# Protection_channel_A_Page_2.net
KiCad netlist of a schematic drawn in Altium Designer
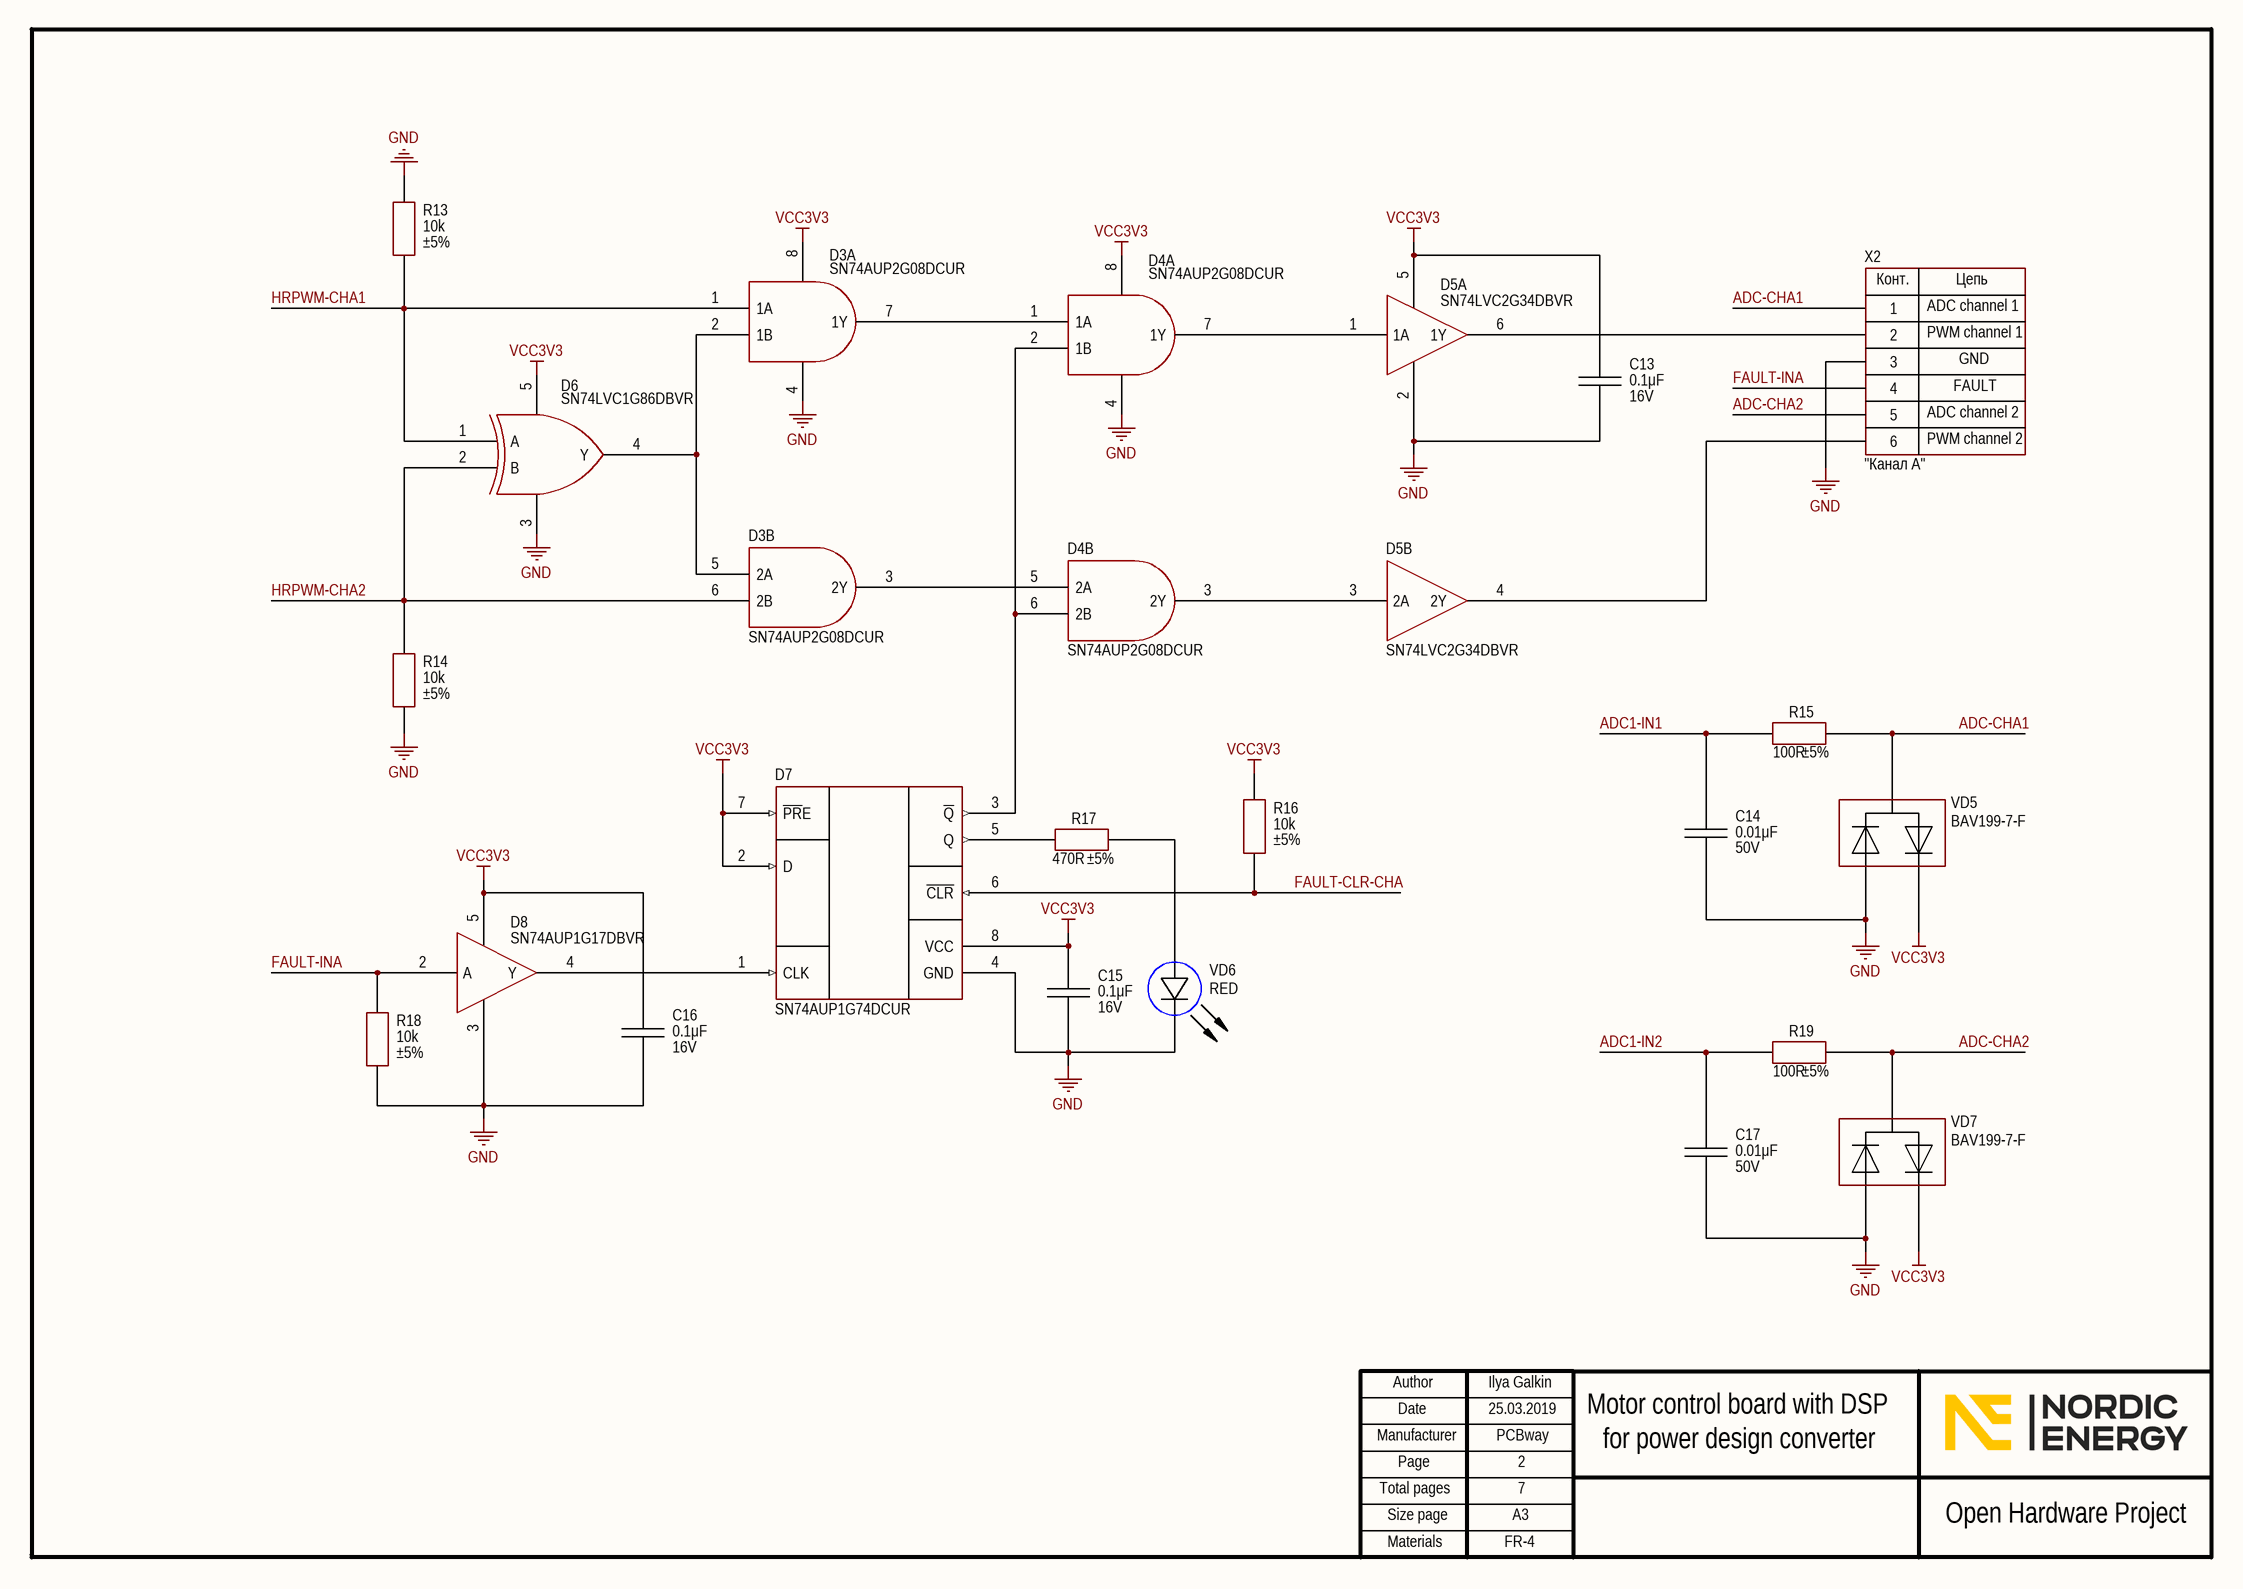
[diagram p0: Protection channel A. Page 2.SchDoc]

(export (version "E")
  (design (tool "Eeschema 10.0.6"))
  (components
    (comp (ref "C13")
      (value "0.1μF")
      (footprint "CAP: 0805")
      (fields
        (field (name "MANUFACTURER") "Yageo")
        (field (name "PARTNUMBER") "CC0805KRX7R7BB104")
        (field (name "VALUEMANUFACTURERPARTNUMBER") "Ceramic capacitor, 0.1μF, X7R, ±10%, 16V, 0805, -55...+125°C")
        (field (name "VOLTAGE") "16V")
      )
      (libsource (lib "Capacitor") (part "Ceramic_0805"))
    )
    (comp (ref "C14")
      (value "0.01μF")
      (footprint "CAP: 0805")
      (fields
        (field (name "MANUFACTURER") "Yageo")
        (field (name "PARTNUMBER") "CC0805KRX7R9BB103")
        (field (name "VALUEMANUFACTURERPARTNUMBER") "Ceramic capacitor, 0.01μF, X7R, ±10%, 50V, 0805, -55...+125°C")
        (field (name "VOLTAGE") "50V")
      )
      (libsource (lib "Capacitor") (part "Ceramic_0805"))
    )
    (comp (ref "C15")
      (value "0.1μF")
      (footprint "CAP: 0805")
      (fields
        (field (name "MANUFACTURER") "Yageo")
        (field (name "PARTNUMBER") "CC0805KRX7R7BB104")
        (field (name "VALUEMANUFACTURERPARTNUMBER") "Ceramic capacitor, 0.1μF, X7R, ±10%, 16V, 0805, -55...+125°C")
        (field (name "VOLTAGE") "16V")
      )
      (libsource (lib "Capacitor") (part "Ceramic_0805"))
    )
    (comp (ref "C16")
      (value "0.1μF")
      (footprint "CAP: 0805")
      (fields
        (field (name "MANUFACTURER") "Yageo")
        (field (name "PARTNUMBER") "CC0805KRX7R7BB104")
        (field (name "VALUEMANUFACTURERPARTNUMBER") "Ceramic capacitor, 0.1μF, X7R, ±10%, 16V, 0805, -55...+125°C")
        (field (name "VOLTAGE") "16V")
      )
      (libsource (lib "Capacitor") (part "Ceramic_0805"))
    )
    (comp (ref "C17")
      (value "0.01μF")
      (footprint "CAP: 0805")
      (fields
        (field (name "MANUFACTURER") "Yageo")
        (field (name "PARTNUMBER") "CC0805KRX7R9BB103")
        (field (name "VALUEMANUFACTURERPARTNUMBER") "Ceramic capacitor, 0.01μF, X7R, ±10%, 50V, 0805, -55...+125°C")
        (field (name "VOLTAGE") "50V")
      )
      (libsource (lib "Capacitor") (part "Ceramic_0805"))
    )
    (comp (ref "D3")
      (value "~")
      (footprint "8-VSSOP")
      (description "AND")
      (fields
        (field (name "MANUFACTURER") "Texas Instruments")
        (field (name "VALUEMANUFACTURERPARTNUMBER") "IC logic AND, 0.8...3.6V, -40...+855°C, 8-VSSOP")
        (field (name "PARTNUMBER") "SN74AUP2G08DCUR")
      )
      (libsource (lib "IC. Logic") (part "SN74AUP2G08DCUR"))
    )
    (comp (ref "D4")
      (value "~")
      (footprint "8-VSSOP")
      (description "AND")
      (fields
        (field (name "MANUFACTURER") "Texas Instruments")
        (field (name "VALUEMANUFACTURERPARTNUMBER") "IC logic AND, 0.8...3.6V, -40...+855°C, 8-VSSOP")
        (field (name "PARTNUMBER") "SN74AUP2G08DCUR")
      )
      (libsource (lib "IC. Logic") (part "SN74AUP2G08DCUR"))
    )
    (comp (ref "D5")
      (value "~")
      (footprint "SOT23-6")
      (description "Buffer")
      (fields
        (field (name "MANUFACTURER") "Texas Instruments")
        (field (name "VALUEMANUFACTURERPARTNUMBER") "IC logic buffer, 1.65...5.5V, -40...+125°C, SOT23-6")
        (field (name "PARTNUMBER") "SN74LVC2G34DBVR")
      )
      (libsource (lib "IC. Logic") (part "SN74LVC2G34DBVR"))
    )
    (comp (ref "D6")
      (value "~")
      (footprint "SOT23-5")
      (description "XOR")
      (fields
        (field (name "MANUFACTURER") "Texas Instruments")
        (field (name "VALUEMANUFACTURERPARTNUMBER") "IC logic XOR, 1.65...5.5V, -40...+125°C, SOT23-5")
        (field (name "PARTNUMBER") "SN74LVC1G86DBVR")
      )
      (libsource (lib "IC. Logic") (part "SN74LVC1G86DBVR"))
    )
    (comp (ref "D7")
      (value "~")
      (footprint "8-VSSOP")
      (description "D-trigger")
      (fields
        (field (name "MANUFACTURER") "Texas Instruments")
        (field (name "VALUEMANUFACTURERPARTNUMBER") "ICtrigger D-type, 0.8...3.6V, -40...+85°C, 8-VSSOP")
        (field (name "PARTNUMBER") "SN74AUP1G74DCUR")
      )
      (libsource (lib "IC. Logic") (part "SN74AUP1G74DCUR"))
    )
    (comp (ref "D8")
      (value "~")
      (footprint "SOT23-5")
      (description "Schmitt trigger")
      (fields
        (field (name "MANUFACTURER") "Texas Instruments")
        (field (name "VALUEMANUFACTURERPARTNUMBER") "IC Schmitt trigger, 0.8...3.6V, -40...+85°C, SOT23-6")
        (field (name "PARTNUMBER") "SN74AUP1G17DBVR")
      )
      (libsource (lib "IC. Logic") (part "SN74AUP1G17DBVR"))
    )
    (comp (ref "R13")
      (value "10k")
      (footprint "RES: 0805")
      (fields
        (field (name "MANUFACTURER") "Yageo")
        (field (name "PARTNUMBER") "RC0805JR-0710KL")
        (field (name "VALUEMANUFACTURERPARTNUMBER") "Resistor film, 10k, ±5%, 0805, 0.125W, -55...+125°C")
        (field (name "TOLERANCE") "±5%")
      )
      (libsource (lib "Resistor") (part "Resistor_0805"))
    )
    (comp (ref "R14")
      (value "10k")
      (footprint "RES: 0805")
      (fields
        (field (name "MANUFACTURER") "Yageo")
        (field (name "PARTNUMBER") "RC0805JR-0710KL")
        (field (name "VALUEMANUFACTURERPARTNUMBER") "Resistor film, 10k, ±5%, 0805, 0.125W, -55...+125°C")
        (field (name "TOLERANCE") "±5%")
      )
      (libsource (lib "Resistor") (part "Resistor_0805"))
    )
    (comp (ref "R15")
      (value "100R")
      (footprint "RES: 0805")
      (fields
        (field (name "MANUFACTURER") "Yageo")
        (field (name "PARTNUMBER") "RC0805JR-07100RL")
        (field (name "VALUEMANUFACTURERPARTNUMBER") "Resistor film, 100R, ±5%, 0805, 0.125W, -55...+125°C")
        (field (name "TOLERANCE") "±5%")
      )
      (libsource (lib "") (part "Resistor_0805_2"))
    )
    (comp (ref "R16")
      (value "10k")
      (footprint "RES: 0805")
      (fields
        (field (name "MANUFACTURER") "Yageo")
        (field (name "PARTNUMBER") "RC0805JR-0710KL")
        (field (name "VALUEMANUFACTURERPARTNUMBER") "Resistor film, 10k, ±5%, 0805, 0.125W, -55...+125°C")
        (field (name "TOLERANCE") "±5%")
      )
      (libsource (lib "Resistor") (part "Resistor_0805"))
    )
    (comp (ref "R17")
      (value "470R")
      (footprint "RES: 0805")
      (fields
        (field (name "MANUFACTURER") "Yageo")
        (field (name "PARTNUMBER") "RC0805JR-07470RL")
        (field (name "VALUEMANUFACTURERPARTNUMBER") "Resistor film, 470R, ±5%, 0805, 0.125W, -55...+125°C")
        (field (name "TOLERANCE") "±5%")
      )
      (libsource (lib "") (part "Resistor_0805_1"))
    )
    (comp (ref "R18")
      (value "10k")
      (footprint "RES: 0805")
      (fields
        (field (name "MANUFACTURER") "Yageo")
        (field (name "PARTNUMBER") "RC0805JR-0710KL")
        (field (name "VALUEMANUFACTURERPARTNUMBER") "Resistor film, 10k, ±5%, 0805, 0.125W, -55...+125°C")
        (field (name "TOLERANCE") "±5%")
      )
      (libsource (lib "Resistor") (part "Resistor_0805"))
    )
    (comp (ref "R19")
      (value "100R")
      (footprint "RES: 0805")
      (fields
        (field (name "MANUFACTURER") "Yageo")
        (field (name "PARTNUMBER") "RC0805JR-07100RL")
        (field (name "VALUEMANUFACTURERPARTNUMBER") "Resistor film, 100R, ±5%, 0805, 0.125W, -55...+125°C")
        (field (name "TOLERANCE") "±5%")
      )
      (libsource (lib "") (part "Resistor_0805_2"))
    )
    (comp (ref "VD5")
      (value "~")
      (footprint "SOT23")
      (fields
        (field (name "MANUFACTURER") "Diodes Incorporated")
        (field (name "VALUEMANUFACTURERPARTNUMBER") "Diode array, 85V, 140mA, 1.1V, 3us, SOT-23, -65...+150°C")
        (field (name "VOLTAGE") "85V")
        (field (name "PARTNUMBER") "BAV199-7-F")
      )
      (libsource (lib "Diode") (part "Diode_array"))
    )
    (comp (ref "VD6")
      (value "~")
      (footprint "LED: 0805R")
      (fields
        (field (name "MANUFACTURER") "Wurth")
        (field (name "VALUEMANUFACTURERPARTNUMBER") "LED, 20mA, 2V, 0805, -55...+150°C")
        (field (name "PARTNUMBER") "150080RS75000")
        (field (name "COLOR") "RED")
      )
      (libsource (lib "Diode") (part "LED_single"))
    )
    (comp (ref "VD7")
      (value "~")
      (footprint "SOT23")
      (fields
        (field (name "MANUFACTURER") "Diodes Incorporated")
        (field (name "VALUEMANUFACTURERPARTNUMBER") "Diode array, 85V, 140mA, 1.1V, 3us, SOT-23, -65...+150°C")
        (field (name "VOLTAGE") "85V")
        (field (name "PARTNUMBER") "BAV199-7-F")
      )
      (libsource (lib "Diode") (part "Diode_array"))
    )
    (comp (ref "X2")
      (value "~")
      (footprint "CON: PLD-6")
      (fields
        (field (name "MANUFACTURER") "Connfly")
        (field (name "VALUEMANUFACTURERPARTNUMBER") "Connector, 6pin, 2.54mm, 500VAC, 3A")
        (field (name "PARTNUMBER") "PLD-6")
        (field (name "COMMENTTEXT") "\"Канал А\"")
      )
      (libsource (lib "Connector") (part "PLD-6"))
    )
  )
  (nets
    (net (code "1") (name "/ADC-CHA1") (class "Default")
      (node (ref "R15") (pin "2") (pinfunction "2_2") (pintype "passive"))
      (node (ref "VD5") (pin "3") (pinfunction "3_3") (pintype "passive"))
      (node (ref "X2") (pin "1") (pinfunction "1_1") (pintype "passive"))
    )
    (net (code "2") (name "/ADC-CHA2") (class "Default")
      (node (ref "R19") (pin "2") (pinfunction "2_2") (pintype "passive"))
      (node (ref "VD7") (pin "3") (pinfunction "3_3") (pintype "passive"))
      (node (ref "X2") (pin "5") (pinfunction "5_5") (pintype "power_in"))
    )
    (net (code "3") (name "/ADC1-IN1") (class "Default")
      (node (ref "C14") (pin "2") (pinfunction "2_2") (pintype "power_in"))
      (node (ref "R15") (pin "1") (pinfunction "1_1") (pintype "passive"))
    )
    (net (code "4") (name "/ADC1-IN2") (class "Default")
      (node (ref "C17") (pin "2") (pinfunction "2_2") (pintype "power_in"))
      (node (ref "R19") (pin "1") (pinfunction "1_1") (pintype "passive"))
    )
    (net (code "5") (name "/FAULT-CLR-CHA") (class "Default")
      (node (ref "D7") (pin "6") (pinfunction "~{CLR}_6") (pintype "input"))
      (node (ref "R16") (pin "2") (pinfunction "2_2") (pintype "passive"))
    )
    (net (code "6") (name "/FAULT-INA") (class "Default")
      (node (ref "D8") (pin "2") (pinfunction "A_2") (pintype "passive"))
      (node (ref "R18") (pin "1") (pinfunction "1_1") (pintype "passive"))
      (node (ref "X2") (pin "4") (pinfunction "4_4") (pintype "power_in"))
    )
    (net (code "7") (name "/HRPWM-CHA1") (class "Default")
      (node (ref "D3") (pin "1") (pinfunction "1A_1") (pintype "passive"))
      (node (ref "D6") (pin "1") (pinfunction "A_1") (pintype "passive"))
      (node (ref "R13") (pin "2") (pinfunction "2_2") (pintype "passive"))
    )
    (net (code "8") (name "/HRPWM-CHA2") (class "Default")
      (node (ref "D3") (pin "6") (pinfunction "2B_6") (pintype "passive"))
      (node (ref "D6") (pin "2") (pinfunction "B_2") (pintype "passive"))
      (node (ref "R14") (pin "1") (pinfunction "1_1") (pintype "passive"))
    )
    (net (code "9") (name "GND") (class "Default")
      (node (ref "C13") (pin "1") (pinfunction "1_1") (pintype "power_in"))
      (node (ref "C14") (pin "1") (pinfunction "1_1") (pintype "power_in"))
      (node (ref "C15") (pin "1") (pinfunction "1_1") (pintype "power_in"))
      (node (ref "C16") (pin "1") (pinfunction "1_1") (pintype "power_in"))
      (node (ref "C17") (pin "1") (pinfunction "1_1") (pintype "power_in"))
      (node (ref "D3") (pin "4") (pintype "passive"))
      (node (ref "D4") (pin "4") (pintype "passive"))
      (node (ref "D5") (pin "2") (pintype "passive"))
      (node (ref "D6") (pin "3") (pintype "passive"))
      (node (ref "D7") (pin "4") (pinfunction "GND_4") (pintype "passive"))
      (node (ref "D8") (pin "3") (pintype "passive"))
      (node (ref "R13") (pin "1") (pinfunction "1_1") (pintype "passive"))
      (node (ref "R14") (pin "2") (pinfunction "2_2") (pintype "passive"))
      (node (ref "R18") (pin "2") (pinfunction "2_2") (pintype "passive"))
      (node (ref "VD5") (pin "1") (pinfunction "1_1") (pintype "passive"))
      (node (ref "VD6") (pin "2") (pinfunction "C_2") (pintype "passive"))
      (node (ref "VD7") (pin "1") (pinfunction "1_1") (pintype "passive"))
      (node (ref "X2") (pin "3") (pinfunction "3_3") (pintype "power_in"))
    )
    (net (code "10") (name "Net-(D3A-1B)") (class "Default")
      (node (ref "D3") (pin "2") (pinfunction "1B_2") (pintype "passive"))
      (node (ref "D3") (pin "5") (pinfunction "2A_5") (pintype "passive"))
      (node (ref "D6") (pin "4") (pinfunction "Y_4") (pintype "passive"))
    )
    (net (code "11") (name "Net-(D3A-1Y)") (class "Default")
      (node (ref "D3") (pin "7") (pinfunction "1Y_7") (pintype "passive"))
      (node (ref "D4") (pin "1") (pinfunction "1A_1") (pintype "passive"))
    )
    (net (code "12") (name "Net-(D3B-2Y)") (class "Default")
      (node (ref "D3") (pin "3") (pinfunction "2Y_3") (pintype "passive"))
      (node (ref "D4") (pin "5") (pinfunction "2A_5") (pintype "passive"))
    )
    (net (code "13") (name "Net-(D4A-1B)") (class "Default")
      (node (ref "D4") (pin "2") (pinfunction "1B_2") (pintype "passive"))
      (node (ref "D4") (pin "6") (pinfunction "2B_6") (pintype "passive"))
      (node (ref "D7") (pin "3") (pinfunction "~{Q}_3") (pintype "output"))
    )
    (net (code "14") (name "Net-(D4A-1Y)") (class "Default")
      (node (ref "D4") (pin "7") (pinfunction "1Y_7") (pintype "passive"))
      (node (ref "D5") (pin "1") (pinfunction "1A_1") (pintype "passive"))
    )
    (net (code "15") (name "Net-(D4B-2Y)") (class "Default")
      (node (ref "D4") (pin "3") (pinfunction "2Y_3") (pintype "passive"))
      (node (ref "D5") (pin "3") (pinfunction "2A_3") (pintype "passive"))
    )
    (net (code "16") (name "Net-(D5A-1Y)") (class "Default")
      (node (ref "D5") (pin "6") (pinfunction "1Y_6") (pintype "passive"))
      (node (ref "X2") (pin "2") (pinfunction "2_2") (pintype "passive"))
    )
    (net (code "17") (name "Net-(D5B-2Y)") (class "Default")
      (node (ref "D5") (pin "4") (pinfunction "2Y_4") (pintype "passive"))
      (node (ref "X2") (pin "6") (pinfunction "6_6") (pintype "power_in"))
    )
    (net (code "18") (name "Net-(D7-CLK)") (class "Default")
      (node (ref "D7") (pin "1") (pinfunction "CLK_1") (pintype "input"))
      (node (ref "D8") (pin "4") (pinfunction "Y_4") (pintype "passive"))
    )
    (net (code "19") (name "Net-(D7-Q)") (class "Default")
      (node (ref "D7") (pin "5") (pinfunction "Q_5") (pintype "output"))
      (node (ref "R17") (pin "2") (pinfunction "2_2") (pintype "passive"))
    )
    (net (code "20") (name "Net-(VD6-A)") (class "Default")
      (node (ref "R17") (pin "1") (pinfunction "1_1") (pintype "passive"))
      (node (ref "VD6") (pin "1") (pinfunction "A_1") (pintype "passive"))
    )
    (net (code "21") (name "VCC3V3") (class "Default")
      (node (ref "C13") (pin "2") (pinfunction "2_2") (pintype "power_in"))
      (node (ref "C15") (pin "2") (pinfunction "2_2") (pintype "power_in"))
      (node (ref "C16") (pin "2") (pinfunction "2_2") (pintype "power_in"))
      (node (ref "D3") (pin "8") (pintype "passive"))
      (node (ref "D4") (pin "8") (pintype "passive"))
      (node (ref "D5") (pin "5") (pintype "passive"))
      (node (ref "D6") (pin "5") (pintype "passive"))
      (node (ref "D7") (pin "2") (pinfunction "D_2") (pintype "input"))
      (node (ref "D7") (pin "7") (pinfunction "~{PR}E_7") (pintype "input"))
      (node (ref "D7") (pin "8") (pinfunction "VCC_8") (pintype "passive"))
      (node (ref "D8") (pin "5") (pintype "passive"))
      (node (ref "R16") (pin "1") (pinfunction "1_1") (pintype "passive"))
      (node (ref "VD5") (pin "2") (pinfunction "2_2") (pintype "passive"))
      (node (ref "VD7") (pin "2") (pinfunction "2_2") (pintype "passive"))
    )
  )
)
